# BigMuff2.net
KiCad netlist of a schematic drawn in EAGLE
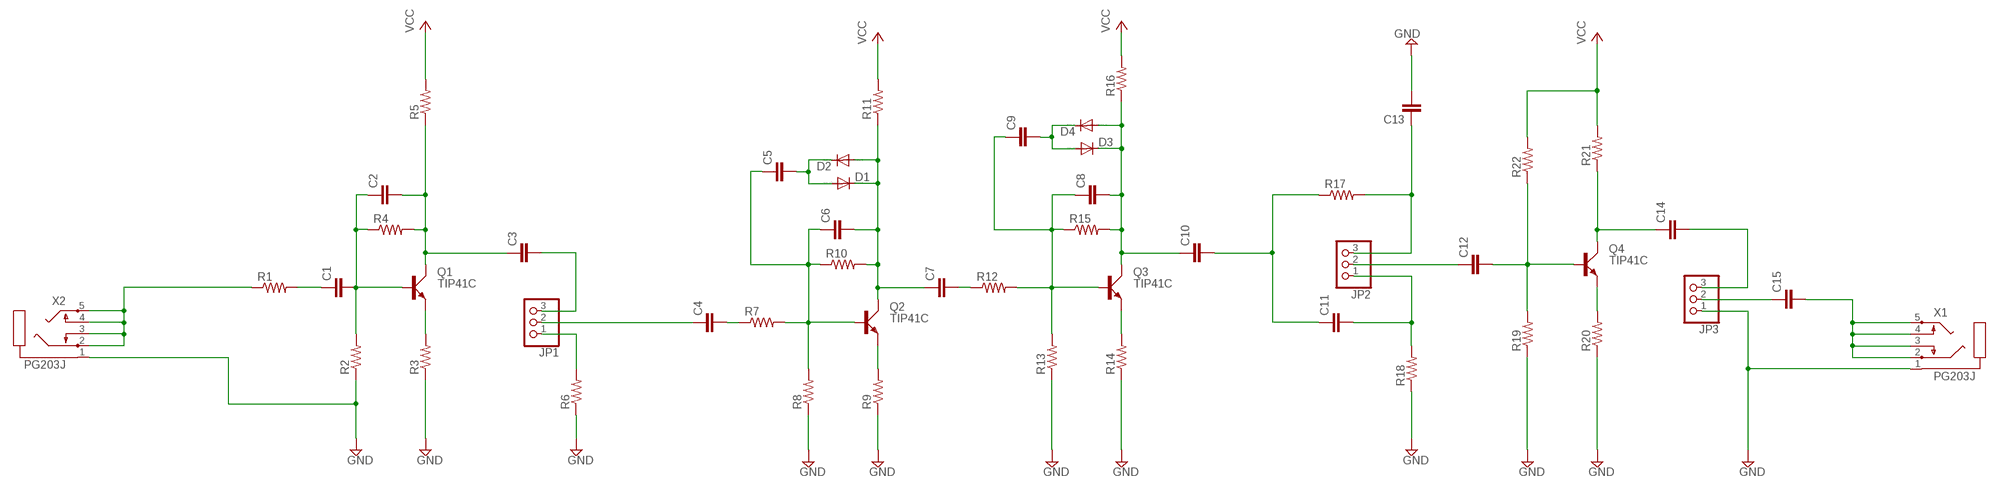
[diagram p0: schematic, sheet 1]

(export (version "E")
  (design (tool "Eeschema 10.0.6"))
  (components
    (comp (ref "C1")
      (value "C2,5-3")
      (footprint "eagle-import:C2.5-3")
      (libsource (lib "eagle-import") (part "C2,5-3"))
    )
    (comp (ref "C2")
      (value "C2,5-3")
      (footprint "eagle-import:C2.5-3")
      (libsource (lib "eagle-import") (part "C2,5-3"))
    )
    (comp (ref "C3")
      (value "C2,5-3")
      (footprint "eagle-import:C2.5-3")
      (libsource (lib "eagle-import") (part "C2,5-3"))
    )
    (comp (ref "C4")
      (value "C2,5-3")
      (footprint "eagle-import:C2.5-3")
      (libsource (lib "eagle-import") (part "C2,5-3"))
    )
    (comp (ref "C5")
      (value "C2,5-3")
      (footprint "eagle-import:C2.5-3")
      (libsource (lib "eagle-import") (part "C2,5-3"))
    )
    (comp (ref "C6")
      (value "C2,5-3")
      (footprint "eagle-import:C2.5-3")
      (libsource (lib "eagle-import") (part "C2,5-3"))
    )
    (comp (ref "C7")
      (value "C2,5-3")
      (footprint "eagle-import:C2.5-3")
      (libsource (lib "eagle-import") (part "C2,5-3"))
    )
    (comp (ref "C8")
      (value "C2,5-3")
      (footprint "eagle-import:C2.5-3")
      (libsource (lib "eagle-import") (part "C2,5-3"))
    )
    (comp (ref "C9")
      (value "C2,5-3")
      (footprint "eagle-import:C2.5-3")
      (libsource (lib "eagle-import") (part "C2,5-3"))
    )
    (comp (ref "C10")
      (value "C2,5-3")
      (footprint "eagle-import:C2.5-3")
      (libsource (lib "eagle-import") (part "C2,5-3"))
    )
    (comp (ref "C11")
      (value "C2,5-3")
      (footprint "eagle-import:C2.5-3")
      (libsource (lib "eagle-import") (part "C2,5-3"))
    )
    (comp (ref "C12")
      (value "C2,5-3")
      (footprint "eagle-import:C2.5-3")
      (libsource (lib "eagle-import") (part "C2,5-3"))
    )
    (comp (ref "C13")
      (value "C2,5-3")
      (footprint "eagle-import:C2.5-3")
      (libsource (lib "eagle-import") (part "C2,5-3"))
    )
    (comp (ref "C14")
      (value "C2,5-3")
      (footprint "eagle-import:C2.5-3")
      (libsource (lib "eagle-import") (part "C2,5-3"))
    )
    (comp (ref "C15")
      (value "C2,5-3")
      (footprint "eagle-import:C2.5-3")
      (libsource (lib "eagle-import") (part "C2,5-3"))
    )
    (comp (ref "D1")
      (value "DIODE-D-2.5")
      (footprint "eagle-import:D-2.5")
      (libsource (lib "eagle-import") (part "DIODE-D-2.5"))
    )
    (comp (ref "D2")
      (value "DIODE-D-2.5")
      (footprint "eagle-import:D-2.5")
      (libsource (lib "eagle-import") (part "DIODE-D-2.5"))
    )
    (comp (ref "D3")
      (value "DIODE-D-2.5")
      (footprint "eagle-import:D-2.5")
      (libsource (lib "eagle-import") (part "DIODE-D-2.5"))
    )
    (comp (ref "D4")
      (value "DIODE-D-2.5")
      (footprint "eagle-import:D-2.5")
      (libsource (lib "eagle-import") (part "DIODE-D-2.5"))
    )
    (comp (ref "JP1")
      (value "PINHD-1X3")
      (footprint "eagle-import:1X03")
      (libsource (lib "eagle-import") (part "PINHD-1X3"))
    )
    (comp (ref "JP2")
      (value "PINHD-1X3")
      (footprint "eagle-import:1X03")
      (libsource (lib "eagle-import") (part "PINHD-1X3"))
    )
    (comp (ref "JP3")
      (value "PINHD-1X3")
      (footprint "eagle-import:1X03")
      (libsource (lib "eagle-import") (part "PINHD-1X3"))
    )
    (comp (ref "Q1")
      (value "TIP41C")
      (footprint "eagle-import:TO220AV")
      (libsource (lib "eagle-import") (part "TIP41C"))
    )
    (comp (ref "Q2")
      (value "TIP41C")
      (footprint "eagle-import:TO220AV")
      (libsource (lib "eagle-import") (part "TIP41C"))
    )
    (comp (ref "Q3")
      (value "TIP41C")
      (footprint "eagle-import:TO220AV")
      (libsource (lib "eagle-import") (part "TIP41C"))
    )
    (comp (ref "Q4")
      (value "TIP41C")
      (footprint "eagle-import:TO220AV")
      (libsource (lib "eagle-import") (part "TIP41C"))
    )
    (comp (ref "R1")
      (value "R-US_0204/2V")
      (footprint "eagle-import:0204V")
      (libsource (lib "eagle-import") (part "R-US_0204/2V"))
    )
    (comp (ref "R2")
      (value "R-US_0204/2V")
      (footprint "eagle-import:0204V")
      (libsource (lib "eagle-import") (part "R-US_0204/2V"))
    )
    (comp (ref "R3")
      (value "R-US_0204/2V")
      (footprint "eagle-import:0204V")
      (libsource (lib "eagle-import") (part "R-US_0204/2V"))
    )
    (comp (ref "R4")
      (value "R-US_0204/2V")
      (footprint "eagle-import:0204V")
      (libsource (lib "eagle-import") (part "R-US_0204/2V"))
    )
    (comp (ref "R5")
      (value "R-US_0204/2V")
      (footprint "eagle-import:0204V")
      (libsource (lib "eagle-import") (part "R-US_0204/2V"))
    )
    (comp (ref "R6")
      (value "R-US_0204/2V")
      (footprint "eagle-import:0204V")
      (libsource (lib "eagle-import") (part "R-US_0204/2V"))
    )
    (comp (ref "R7")
      (value "R-US_0204/2V")
      (footprint "eagle-import:0204V")
      (libsource (lib "eagle-import") (part "R-US_0204/2V"))
    )
    (comp (ref "R8")
      (value "R-US_0204/2V")
      (footprint "eagle-import:0204V")
      (libsource (lib "eagle-import") (part "R-US_0204/2V"))
    )
    (comp (ref "R9")
      (value "R-US_0204/2V")
      (footprint "eagle-import:0204V")
      (libsource (lib "eagle-import") (part "R-US_0204/2V"))
    )
    (comp (ref "R10")
      (value "R-US_0204/2V")
      (footprint "eagle-import:0204V")
      (libsource (lib "eagle-import") (part "R-US_0204/2V"))
    )
    (comp (ref "R11")
      (value "R-US_0204/2V")
      (footprint "eagle-import:0204V")
      (libsource (lib "eagle-import") (part "R-US_0204/2V"))
    )
    (comp (ref "R12")
      (value "R-US_0204/2V")
      (footprint "eagle-import:0204V")
      (libsource (lib "eagle-import") (part "R-US_0204/2V"))
    )
    (comp (ref "R13")
      (value "R-US_0204/2V")
      (footprint "eagle-import:0204V")
      (libsource (lib "eagle-import") (part "R-US_0204/2V"))
    )
    (comp (ref "R14")
      (value "R-US_0204/2V")
      (footprint "eagle-import:0204V")
      (libsource (lib "eagle-import") (part "R-US_0204/2V"))
    )
    (comp (ref "R15")
      (value "R-US_0204/2V")
      (footprint "eagle-import:0204V")
      (libsource (lib "eagle-import") (part "R-US_0204/2V"))
    )
    (comp (ref "R16")
      (value "R-US_0204/2V")
      (footprint "eagle-import:0204V")
      (libsource (lib "eagle-import") (part "R-US_0204/2V"))
    )
    (comp (ref "R17")
      (value "R-US_0204/2V")
      (footprint "eagle-import:0204V")
      (libsource (lib "eagle-import") (part "R-US_0204/2V"))
    )
    (comp (ref "R18")
      (value "R-US_0204/2V")
      (footprint "eagle-import:0204V")
      (libsource (lib "eagle-import") (part "R-US_0204/2V"))
    )
    (comp (ref "R19")
      (value "R-US_0204/2V")
      (footprint "eagle-import:0204V")
      (libsource (lib "eagle-import") (part "R-US_0204/2V"))
    )
    (comp (ref "R20")
      (value "R-US_0204/2V")
      (footprint "eagle-import:0204V")
      (libsource (lib "eagle-import") (part "R-US_0204/2V"))
    )
    (comp (ref "R21")
      (value "R-US_0204/2V")
      (footprint "eagle-import:0204V")
      (libsource (lib "eagle-import") (part "R-US_0204/2V"))
    )
    (comp (ref "R22")
      (value "R-US_0204/2V")
      (footprint "eagle-import:0204V")
      (libsource (lib "eagle-import") (part "R-US_0204/2V"))
    )
    (comp (ref "X1")
      (value "PG203J")
      (footprint "eagle-import:PG203J")
      (libsource (lib "eagle-import") (part "PG203J"))
    )
    (comp (ref "X2")
      (value "PG203J")
      (footprint "eagle-import:PG203J")
      (libsource (lib "eagle-import") (part "PG203J"))
    )
  )
  (nets
    (net (code "1") (name "GND") (class "Default")
      (node (ref "C13") (pin "2") (pinfunction "2_2") (pintype "passive"))
      (node (ref "JP3") (pin "1") (pinfunction "1_1") (pintype "passive"))
      (node (ref "R13") (pin "1") (pinfunction "1_1") (pintype "passive"))
      (node (ref "R14") (pin "1") (pinfunction "1_1") (pintype "passive"))
      (node (ref "R18") (pin "1") (pinfunction "1_1") (pintype "passive"))
      (node (ref "R19") (pin "1") (pinfunction "1_1") (pintype "passive"))
      (node (ref "R2") (pin "1") (pinfunction "1_1") (pintype "passive"))
      (node (ref "R20") (pin "1") (pinfunction "1_1") (pintype "passive"))
      (node (ref "R3") (pin "1") (pinfunction "1_1") (pintype "passive"))
      (node (ref "R6") (pin "1") (pinfunction "1_1") (pintype "passive"))
      (node (ref "R8") (pin "1") (pinfunction "1_1") (pintype "passive"))
      (node (ref "R9") (pin "1") (pinfunction "1_1") (pintype "passive"))
      (node (ref "X1") (pin "1") (pinfunction "1_1") (pintype "passive"))
      (node (ref "X2") (pin "1") (pinfunction "1_1") (pintype "passive"))
    )
    (net (code "2") (name "Net-(C1-Pad1)") (class "Default")
      (node (ref "C1") (pin "1") (pinfunction "1_1") (pintype "passive"))
      (node (ref "R1") (pin "2") (pinfunction "2_2") (pintype "passive"))
    )
    (net (code "3") (name "Net-(C1-Pad2)") (class "Default")
      (node (ref "C1") (pin "2") (pinfunction "2_2") (pintype "passive"))
      (node (ref "C2") (pin "1") (pinfunction "1_1") (pintype "passive"))
      (node (ref "Q1") (pin "B") (pinfunction "B_B") (pintype "passive"))
      (node (ref "R2") (pin "2") (pinfunction "2_2") (pintype "passive"))
      (node (ref "R4") (pin "1") (pinfunction "1_1") (pintype "passive"))
    )
    (net (code "4") (name "Net-(C2-Pad2)") (class "Default")
      (node (ref "C2") (pin "2") (pinfunction "2_2") (pintype "passive"))
      (node (ref "C3") (pin "1") (pinfunction "1_1") (pintype "passive"))
      (node (ref "Q1") (pin "C") (pinfunction "C_C") (pintype "passive"))
      (node (ref "R4") (pin "2") (pinfunction "2_2") (pintype "passive"))
      (node (ref "R5") (pin "1") (pinfunction "1_1") (pintype "passive"))
    )
    (net (code "5") (name "Net-(C3-Pad2)") (class "Default")
      (node (ref "C3") (pin "2") (pinfunction "2_2") (pintype "passive"))
      (node (ref "JP1") (pin "3") (pinfunction "3_3") (pintype "passive"))
    )
    (net (code "6") (name "Net-(C4-Pad1)") (class "Default")
      (node (ref "C4") (pin "1") (pinfunction "1_1") (pintype "passive"))
      (node (ref "JP1") (pin "2") (pinfunction "2_2") (pintype "passive"))
    )
    (net (code "7") (name "Net-(C4-Pad2)") (class "Default")
      (node (ref "C4") (pin "2") (pinfunction "2_2") (pintype "passive"))
      (node (ref "R7") (pin "1") (pinfunction "1_1") (pintype "passive"))
    )
    (net (code "8") (name "Net-(C5-Pad1)") (class "Default")
      (node (ref "C5") (pin "1") (pinfunction "1_1") (pintype "passive"))
      (node (ref "C6") (pin "1") (pinfunction "1_1") (pintype "passive"))
      (node (ref "Q2") (pin "B") (pinfunction "B_B") (pintype "passive"))
      (node (ref "R10") (pin "1") (pinfunction "1_1") (pintype "passive"))
      (node (ref "R7") (pin "2") (pinfunction "2_2") (pintype "passive"))
      (node (ref "R8") (pin "2") (pinfunction "2_2") (pintype "passive"))
    )
    (net (code "9") (name "Net-(C5-Pad2)") (class "Default")
      (node (ref "C5") (pin "2") (pinfunction "2_2") (pintype "passive"))
      (node (ref "D1") (pin "A") (pinfunction "A_A") (pintype "passive"))
      (node (ref "D2") (pin "C") (pinfunction "C_C") (pintype "passive"))
    )
    (net (code "10") (name "Net-(C6-Pad2)") (class "Default")
      (node (ref "C6") (pin "2") (pinfunction "2_2") (pintype "passive"))
      (node (ref "C7") (pin "1") (pinfunction "1_1") (pintype "passive"))
      (node (ref "D1") (pin "C") (pinfunction "C_C") (pintype "passive"))
      (node (ref "D2") (pin "A") (pinfunction "A_A") (pintype "passive"))
      (node (ref "Q2") (pin "C") (pinfunction "C_C") (pintype "passive"))
      (node (ref "R10") (pin "2") (pinfunction "2_2") (pintype "passive"))
      (node (ref "R11") (pin "1") (pinfunction "1_1") (pintype "passive"))
    )
    (net (code "11") (name "Net-(C7-Pad2)") (class "Default")
      (node (ref "C7") (pin "2") (pinfunction "2_2") (pintype "passive"))
      (node (ref "R12") (pin "1") (pinfunction "1_1") (pintype "passive"))
    )
    (net (code "12") (name "Net-(C8-Pad1)") (class "Default")
      (node (ref "C8") (pin "1") (pinfunction "1_1") (pintype "passive"))
      (node (ref "C9") (pin "1") (pinfunction "1_1") (pintype "passive"))
      (node (ref "Q3") (pin "B") (pinfunction "B_B") (pintype "passive"))
      (node (ref "R12") (pin "2") (pinfunction "2_2") (pintype "passive"))
      (node (ref "R13") (pin "2") (pinfunction "2_2") (pintype "passive"))
      (node (ref "R15") (pin "1") (pinfunction "1_1") (pintype "passive"))
    )
    (net (code "13") (name "Net-(C9-Pad2)") (class "Default")
      (node (ref "C9") (pin "2") (pinfunction "2_2") (pintype "passive"))
      (node (ref "D3") (pin "A") (pinfunction "A_A") (pintype "passive"))
      (node (ref "D4") (pin "C") (pinfunction "C_C") (pintype "passive"))
    )
    (net (code "14") (name "Net-(C10-Pad1)") (class "Default")
      (node (ref "C10") (pin "1") (pinfunction "1_1") (pintype "passive"))
      (node (ref "C8") (pin "2") (pinfunction "2_2") (pintype "passive"))
      (node (ref "D3") (pin "C") (pinfunction "C_C") (pintype "passive"))
      (node (ref "D4") (pin "A") (pinfunction "A_A") (pintype "passive"))
      (node (ref "Q3") (pin "C") (pinfunction "C_C") (pintype "passive"))
      (node (ref "R15") (pin "2") (pinfunction "2_2") (pintype "passive"))
      (node (ref "R16") (pin "1") (pinfunction "1_1") (pintype "passive"))
    )
    (net (code "15") (name "Net-(C10-Pad2)") (class "Default")
      (node (ref "C10") (pin "2") (pinfunction "2_2") (pintype "passive"))
      (node (ref "C11") (pin "1") (pinfunction "1_1") (pintype "passive"))
      (node (ref "R17") (pin "1") (pinfunction "1_1") (pintype "passive"))
    )
    (net (code "16") (name "Net-(C11-Pad2)") (class "Default")
      (node (ref "C11") (pin "2") (pinfunction "2_2") (pintype "passive"))
      (node (ref "JP2") (pin "1") (pinfunction "1_1") (pintype "passive"))
      (node (ref "R18") (pin "2") (pinfunction "2_2") (pintype "passive"))
    )
    (net (code "17") (name "Net-(C12-Pad1)") (class "Default")
      (node (ref "C12") (pin "1") (pinfunction "1_1") (pintype "passive"))
      (node (ref "JP2") (pin "2") (pinfunction "2_2") (pintype "passive"))
    )
    (net (code "18") (name "Net-(C12-Pad2)") (class "Default")
      (node (ref "C12") (pin "2") (pinfunction "2_2") (pintype "passive"))
      (node (ref "Q4") (pin "B") (pinfunction "B_B") (pintype "passive"))
      (node (ref "R19") (pin "2") (pinfunction "2_2") (pintype "passive"))
      (node (ref "R22") (pin "1") (pinfunction "1_1") (pintype "passive"))
    )
    (net (code "19") (name "Net-(C13-Pad1)") (class "Default")
      (node (ref "C13") (pin "1") (pinfunction "1_1") (pintype "passive"))
      (node (ref "JP2") (pin "3") (pinfunction "3_3") (pintype "passive"))
      (node (ref "R17") (pin "2") (pinfunction "2_2") (pintype "passive"))
    )
    (net (code "20") (name "Net-(C14-Pad1)") (class "Default")
      (node (ref "C14") (pin "1") (pinfunction "1_1") (pintype "passive"))
      (node (ref "Q4") (pin "C") (pinfunction "C_C") (pintype "passive"))
      (node (ref "R21") (pin "1") (pinfunction "1_1") (pintype "passive"))
    )
    (net (code "21") (name "Net-(C14-Pad2)") (class "Default")
      (node (ref "C14") (pin "2") (pinfunction "2_2") (pintype "passive"))
      (node (ref "JP3") (pin "3") (pinfunction "3_3") (pintype "passive"))
    )
    (net (code "22") (name "Net-(C15-Pad1)") (class "Default")
      (node (ref "C15") (pin "1") (pinfunction "1_1") (pintype "passive"))
      (node (ref "JP3") (pin "2") (pinfunction "2_2") (pintype "passive"))
    )
    (net (code "23") (name "Net-(C15-Pad2)") (class "Default")
      (node (ref "C15") (pin "2") (pinfunction "2_2") (pintype "passive"))
      (node (ref "X1") (pin "2") (pinfunction "2_2") (pintype "passive"))
      (node (ref "X1") (pin "3") (pinfunction "3_3") (pintype "passive"))
      (node (ref "X1") (pin "4") (pinfunction "4_4") (pintype "passive"))
      (node (ref "X1") (pin "5") (pinfunction "5_5") (pintype "passive"))
    )
    (net (code "24") (name "Net-(JP1-Pad1)") (class "Default")
      (node (ref "JP1") (pin "1") (pinfunction "1_1") (pintype "passive"))
      (node (ref "R6") (pin "2") (pinfunction "2_2") (pintype "passive"))
    )
    (net (code "25") (name "Net-(Q1-PadE)") (class "Default")
      (node (ref "Q1") (pin "E") (pinfunction "E_E") (pintype "passive"))
      (node (ref "R3") (pin "2") (pinfunction "2_2") (pintype "passive"))
    )
    (net (code "26") (name "Net-(Q2-PadE)") (class "Default")
      (node (ref "Q2") (pin "E") (pinfunction "E_E") (pintype "passive"))
      (node (ref "R9") (pin "2") (pinfunction "2_2") (pintype "passive"))
    )
    (net (code "27") (name "Net-(Q3-PadE)") (class "Default")
      (node (ref "Q3") (pin "E") (pinfunction "E_E") (pintype "passive"))
      (node (ref "R14") (pin "2") (pinfunction "2_2") (pintype "passive"))
    )
    (net (code "28") (name "Net-(Q4-PadE)") (class "Default")
      (node (ref "Q4") (pin "E") (pinfunction "E_E") (pintype "passive"))
      (node (ref "R20") (pin "2") (pinfunction "2_2") (pintype "passive"))
    )
    (net (code "29") (name "Net-(R1-Pad1)") (class "Default")
      (node (ref "R1") (pin "1") (pinfunction "1_1") (pintype "passive"))
      (node (ref "X2") (pin "2") (pinfunction "2_2") (pintype "passive"))
      (node (ref "X2") (pin "3") (pinfunction "3_3") (pintype "passive"))
      (node (ref "X2") (pin "4") (pinfunction "4_4") (pintype "passive"))
      (node (ref "X2") (pin "5") (pinfunction "5_5") (pintype "passive"))
    )
    (net (code "30") (name "VCC") (class "Default")
      (node (ref "R11") (pin "2") (pinfunction "2_2") (pintype "passive"))
      (node (ref "R16") (pin "2") (pinfunction "2_2") (pintype "passive"))
      (node (ref "R21") (pin "2") (pinfunction "2_2") (pintype "passive"))
      (node (ref "R22") (pin "2") (pinfunction "2_2") (pintype "passive"))
      (node (ref "R5") (pin "2") (pinfunction "2_2") (pintype "passive"))
    )
  )
)
